# Power_Supply_TPS54260.net
KiCad netlist of a schematic drawn in Altium Designer
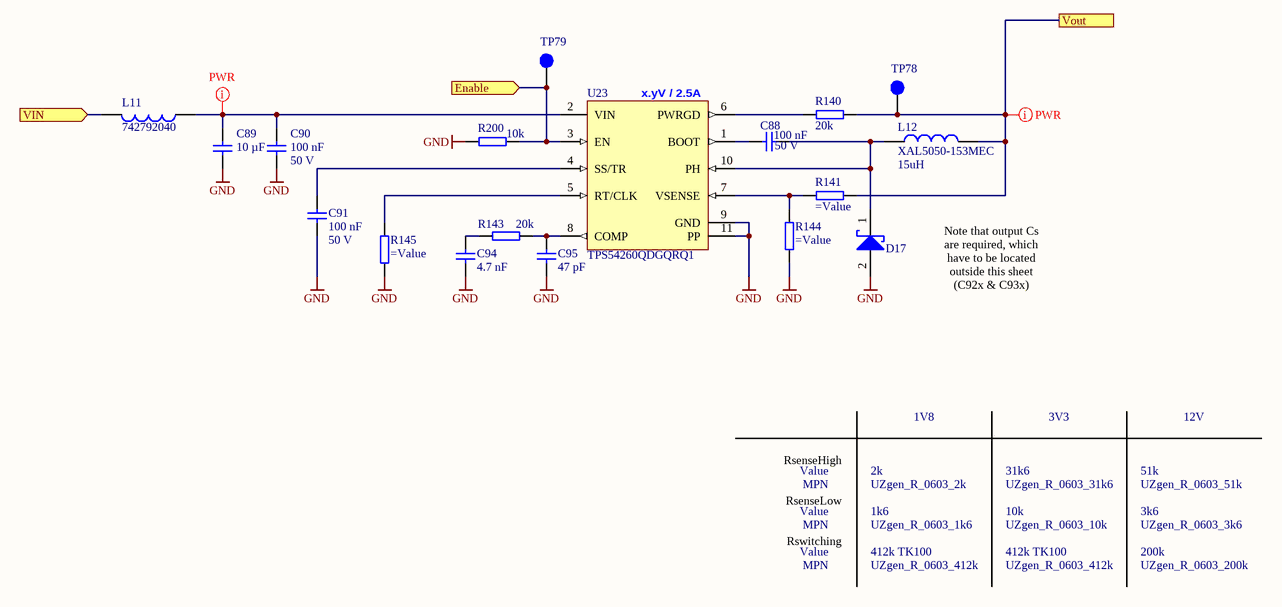
[diagram p0: Power_Supply_TPS54260.SchDoc]

(export (version "E")
  (design (tool "Eeschema 10.0.6"))
  (components
    (comp (ref "C88")
      (value "100 nF")
      (footprint "C_0603_TE")
      (description "Generic capacitor")
      (fields
        (field (name "TOLERANCE") "10 %")
        (field (name "VOLTAGE") "50 V")
        (field (name "MANUFACTURER PART NUMBER") "UZgen_C_0603_100nF_50V_X7R")
        (field (name "CREATED FROM") "AGeiger")
      )
      (libsource (lib "user") (part "CAP-NP"))
    )
    (comp (ref "C89")
      (value "10 µF")
      (footprint "C_1206_TE")
      (description "50V 10uF X7R ±10% 1206  Multilayer Ceramic Capacitors MLCC - SMD/SMT ROHS")
      (fields
        (field (name "TOLERANCE") "10 %")
        (field (name "MANUFACTURER PART NUMBER") "CL31B106KBHNNNE")
        (field (name "CREATED FROM") "AGeiger")
      )
      (libsource (lib "user") (part "CAP-NP"))
    )
    (comp (ref "C90")
      (value "100 nF")
      (footprint "C_0603_TE")
      (description "Generic capacitor")
      (fields
        (field (name "TOLERANCE") "10 %")
        (field (name "VOLTAGE") "50 V")
        (field (name "MANUFACTURER PART NUMBER") "UZgen_C_0603_100nF_50V_X7R")
        (field (name "CREATED FROM") "AGeiger")
      )
      (libsource (lib "user") (part "CAP-NP"))
    )
    (comp (ref "C91")
      (value "100 nF")
      (footprint "C_0603_TE")
      (description "Generic capacitor")
      (fields
        (field (name "TOLERANCE") "10 %")
        (field (name "VOLTAGE") "50 V")
        (field (name "MANUFACTURER PART NUMBER") "UZgen_C_0603_100nF_50V_X7R")
        (field (name "CREATED FROM") "AGeiger")
      )
      (libsource (lib "user") (part "CAP-NP"))
    )
    (comp (ref "C94")
      (value "4.7 nF")
      (footprint "C_0603_TE")
      (description "50V 4.7nF C0G ±5% 0603 Multilayer Ceramic Capacitors MLCC")
      (fields
        (field (name "TOLERANCE") "5%")
        (field (name "MANUFACTURER PART NUMBER") "GRM1885C1H472JA01D")
        (field (name "CREATED FROM") "MGeier")
      )
      (libsource (lib "user") (part "CAP-NP"))
    )
    (comp (ref "C95")
      (value "47 pF")
      (footprint "C_0603_TE")
      (description "50V 47pF C0G ±5% 0603 Multilayer Ceramic Capacitors MLCC")
      (fields
        (field (name "TOLERANCE") "5%")
        (field (name "MANUFACTURER PART NUMBER") "CL10C470JB8NNNC")
        (field (name "CREATED FROM") "MGeier")
      )
      (libsource (lib "user") (part "CAP-NP"))
    )
    (comp (ref "D17")
      (value "STPS340UY")
      (footprint "SMB")
      (description "Power Schottky Rectifier, 3 A, 40 V, 0.57 µF")
      (fields
        (field (name "MANUFACTURER") "STMicroelectronics")
        (field (name "LCSC PART NUMBER") "C283520")
        (field (name "CREATED FROM") "MGremer")
      )
      (libsource (lib "user") (part "STPS340-Y"))
    )
    (comp (ref "L11")
      (value "742792040")
      (footprint "WE-CBF_0805_High Current")
      (description "Inductance, 0805, 100 MHz, 600 Ohm, 2 A")
      (fields
        (field (name "MANUFACTURER") "Wuerth Elektronik")
        (field (name "LCSC PART NUMBER") "C2661857")
        (field (name "CREATED FROM") "AGeiger")
      )
      (libsource (lib "user") (part "WE-CBF"))
    )
    (comp (ref "L12")
      (value "XAL5050-153MEC")
      (footprint "XAL5050153MEC")
      (description "15uH@1MHz  ±20%, 3.9A, 76.7mOhm")
      (fields
        (field (name "ALTIUM_VALUE") "15uH")
        (field (name "MF") "EPCOS / TDK")
        (field (name "MPN") "B82464G4154M")
        (field (name "CREATED FROM") "FRosner")
      )
      (libsource (lib "user") (part "B82464G4154M"))
    )
    (comp (ref "R140")
      (value "20k")
      (footprint "R_0603_TE")
      (description "Generic resistor")
      (fields
        (field (name "TOLERANCE") "1 %")
        (field (name "MANUFACTURER PART NUMBER") "UZgen_R_0603_20k")
        (field (name "CREATED FROM") "UZgenTool")
      )
      (libsource (lib "user") (part "RES"))
    )
    (comp (ref "R141")
      (value "~")
      (footprint "R_0603_TE")
      (description "Generic resistor (parametric)")
      (fields
        (field (name "TOLERANCE") "1 %")
        (field (name "MANUFACTURER") "UZgen")
        (field (name "CREATED FROM") "UZgenTool")
      )
      (libsource (lib "user") (part "RES"))
    )
    (comp (ref "R143")
      (value "20k")
      (footprint "R_0603_TE")
      (description "Generic resistor")
      (fields
        (field (name "TOLERANCE") "1 %")
        (field (name "MANUFACTURER PART NUMBER") "UZgen_R_0603_20k")
        (field (name "CREATED FROM") "UZgenTool")
      )
      (libsource (lib "user") (part "RES"))
    )
    (comp (ref "R144")
      (value "~")
      (footprint "R_0603_TE")
      (description "Generic resistor (parametric)")
      (fields
        (field (name "TOLERANCE") "1 %")
        (field (name "MANUFACTURER") "UZgen")
        (field (name "CREATED FROM") "UZgenTool")
      )
      (libsource (lib "user") (part "RES"))
    )
    (comp (ref "R145")
      (value "~")
      (footprint "R_0603_TE")
      (description "Generic resistor (parametric)")
      (fields
        (field (name "MANUFACTURER") "UZgen")
        (field (name "TOLERANCE") "1 %")
        (field (name "CREATED FROM") "UZgenTool")
      )
      (libsource (lib "user") (part "RES"))
    )
    (comp (ref "R200")
      (value "10k")
      (footprint "R_0603_TE")
      (description "Generic resistor")
      (fields
        (field (name "TOLERANCE") "1 %")
        (field (name "MANUFACTURER PART NUMBER") "UZgen_R_0603_10k")
        (field (name "CREATED FROM") "AGeiger")
      )
      (libsource (lib "user") (part "RES"))
    )
    (comp (ref "TP78")
      (value "Testpoint 1mm")
      (footprint "TP_1mm")
      (fields
        (field (name "MANUFACTURER PART NUMBER") "NULL")
        (field (name "CREATED") "2018_06_25_AGeiger")
        (field (name "CREATED FROM") "AGeiger")
      )
      (libsource (lib "user") (part "TP_1mm"))
    )
    (comp (ref "TP79")
      (value "Testpoint 1mm")
      (footprint "TP_1mm")
      (fields
        (field (name "MANUFACTURER PART NUMBER") "NULL")
        (field (name "CREATED") "2018_06_25_AGeiger")
        (field (name "CREATED FROM") "AGeiger")
      )
      (libsource (lib "user") (part "TP_1mm"))
    )
    (comp (ref "U23")
      (value "TPS54260QDGQRQ1")
      (footprint "TSOP-10_DGQ0010D_N")
      (description "High Efficiency Step-Down Converter, MSOP Package, 2.5 A, 3.5 - 60 V input, adjustable output")
      (fields
        (field (name "MANUFACTURER") "Texas Instruments")
        (field (name "LCSC PART NUMBER") "C181278")
        (field (name "CREATED FROM") "MGremer")
      )
      (libsource (lib "user") (part "TI-TPS54260-Q1"))
    )
  )
  (nets
    (net (code "1") (name "/Enable") (class "Default")
      (node (ref "R200") (pin "2") (pinfunction "2_2") (pintype "passive"))
      (node (ref "TP79") (pin "1") (pintype "passive"))
      (node (ref "U23") (pin "3") (pinfunction "EN_3") (pintype "input"))
    )
    (net (code "2") (name "/VIN") (class "Default")
      (node (ref "L11") (pin "2") (pinfunction "2_2") (pintype "passive"))
    )
    (net (code "3") (name "/Vout") (class "Default")
      (node (ref "L12") (pin "2") (pinfunction "2_2") (pintype "passive"))
      (node (ref "R140") (pin "1") (pinfunction "1_1") (pintype "passive"))
      (node (ref "R141") (pin "1") (pinfunction "1_1") (pintype "passive"))
      (node (ref "TP78") (pin "1") (pintype "passive"))
    )
    (net (code "4") (name "GND") (class "Default")
      (node (ref "C89") (pin "2") (pinfunction "2_2") (pintype "passive"))
      (node (ref "C90") (pin "1") (pinfunction "1_1") (pintype "passive"))
      (node (ref "C91") (pin "1") (pinfunction "1_1") (pintype "passive"))
      (node (ref "C94") (pin "2") (pinfunction "2_2") (pintype "passive"))
      (node (ref "C95") (pin "2") (pinfunction "2_2") (pintype "passive"))
      (node (ref "D17") (pin "2") (pinfunction "A_2") (pintype "passive"))
      (node (ref "R144") (pin "2") (pinfunction "2_2") (pintype "passive"))
      (node (ref "R145") (pin "2") (pinfunction "2_2") (pintype "passive"))
      (node (ref "R200") (pin "1") (pinfunction "1_1") (pintype "passive"))
      (node (ref "U23") (pin "11") (pinfunction "PP_11") (pintype "power_in"))
      (node (ref "U23") (pin "9") (pinfunction "GND_9") (pintype "power_in"))
    )
    (net (code "5") (name "Net-(C94-Pad1)") (class "Default")
      (node (ref "C94") (pin "1") (pinfunction "1_1") (pintype "passive"))
      (node (ref "R143") (pin "2") (pinfunction "2_2") (pintype "passive"))
    )
    (net (code "6") (name "Net-(D17-K)") (class "Default")
      (node (ref "C88") (pin "1") (pinfunction "1_1") (pintype "passive"))
      (node (ref "D17") (pin "1") (pinfunction "K_1") (pintype "passive"))
      (node (ref "L12") (pin "1") (pinfunction "1_1") (pintype "passive"))
      (node (ref "U23") (pin "10") (pinfunction "PH_10") (pintype "input"))
    )
    (net (code "7") (name "Net-(U23-BOOT)") (class "Default")
      (node (ref "C88") (pin "2") (pinfunction "2_2") (pintype "passive"))
      (node (ref "U23") (pin "1") (pinfunction "BOOT_1") (pintype "output"))
    )
    (net (code "8") (name "Net-(U23-COMP)") (class "Default")
      (node (ref "C95") (pin "1") (pinfunction "1_1") (pintype "passive"))
      (node (ref "R143") (pin "1") (pinfunction "1_1") (pintype "passive"))
      (node (ref "U23") (pin "8") (pinfunction "COMP_8") (pintype "output"))
    )
    (net (code "9") (name "Net-(U23-PWRGD)") (class "Default")
      (node (ref "R140") (pin "2") (pinfunction "2_2") (pintype "passive"))
      (node (ref "U23") (pin "6") (pinfunction "PWRGD_6") (pintype "output"))
    )
    (net (code "10") (name "Net-(U23-RT{slash}CLK)") (class "Default")
      (node (ref "R145") (pin "1") (pinfunction "1_1") (pintype "passive"))
      (node (ref "U23") (pin "5") (pinfunction "RT/CLK_5") (pintype "input"))
    )
    (net (code "11") (name "Net-(U23-SS{slash}TR)") (class "Default")
      (node (ref "C91") (pin "2") (pinfunction "2_2") (pintype "passive"))
      (node (ref "U23") (pin "4") (pinfunction "SS/TR_4") (pintype "input"))
    )
    (net (code "12") (name "Net-(U23-VIN)") (class "Default")
      (node (ref "C89") (pin "1") (pinfunction "1_1") (pintype "passive"))
      (node (ref "C90") (pin "2") (pinfunction "2_2") (pintype "passive"))
      (node (ref "L11") (pin "1") (pinfunction "1_1") (pintype "passive"))
      (node (ref "U23") (pin "2") (pinfunction "VIN_2") (pintype "power_in"))
    )
    (net (code "13") (name "Net-(U23-VSENSE)") (class "Default")
      (node (ref "R141") (pin "2") (pinfunction "2_2") (pintype "passive"))
      (node (ref "R144") (pin "1") (pinfunction "1_1") (pintype "passive"))
      (node (ref "U23") (pin "7") (pinfunction "VSENSE_7") (pintype "input"))
    )
  )
)
